# power_Rev_2.net
KiCad netlist of a schematic drawn in EAGLE
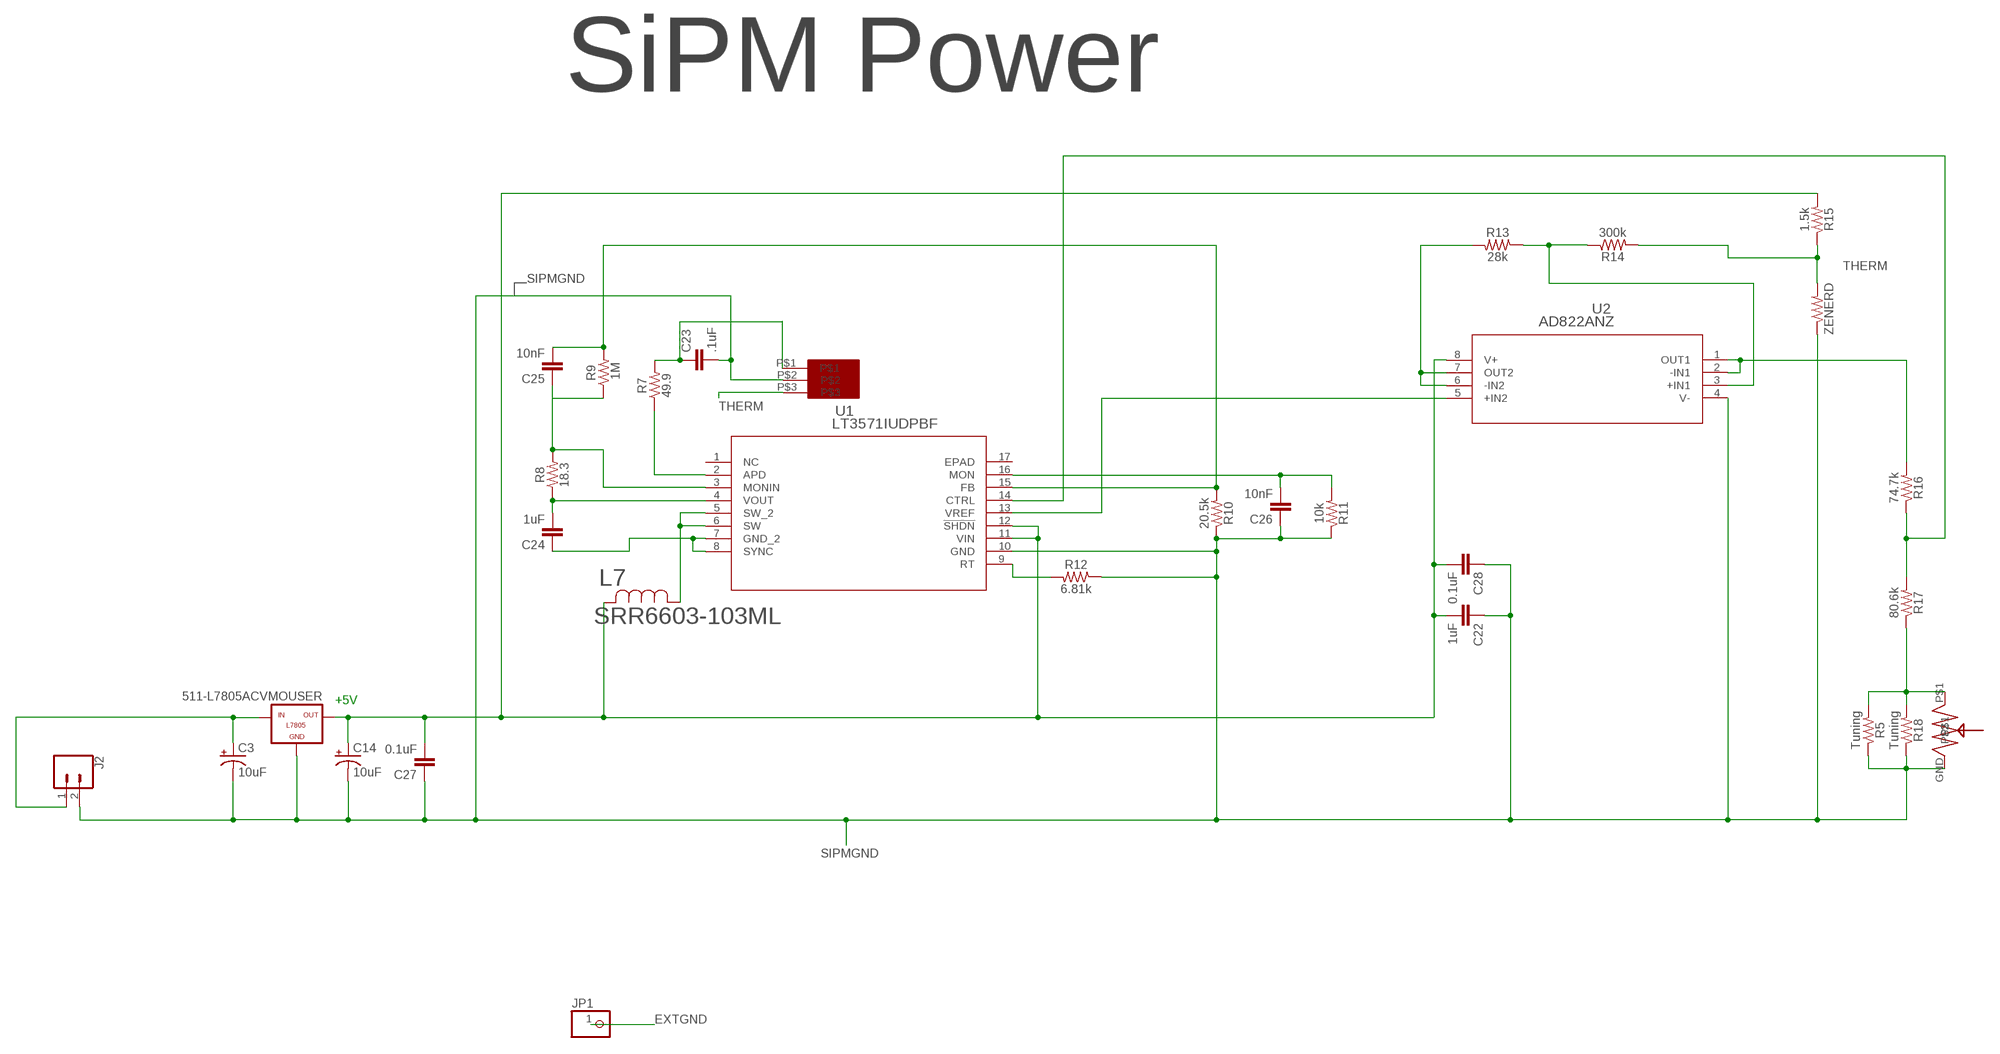
[diagram p0: schematic, sheet 1, part 1 of 2]
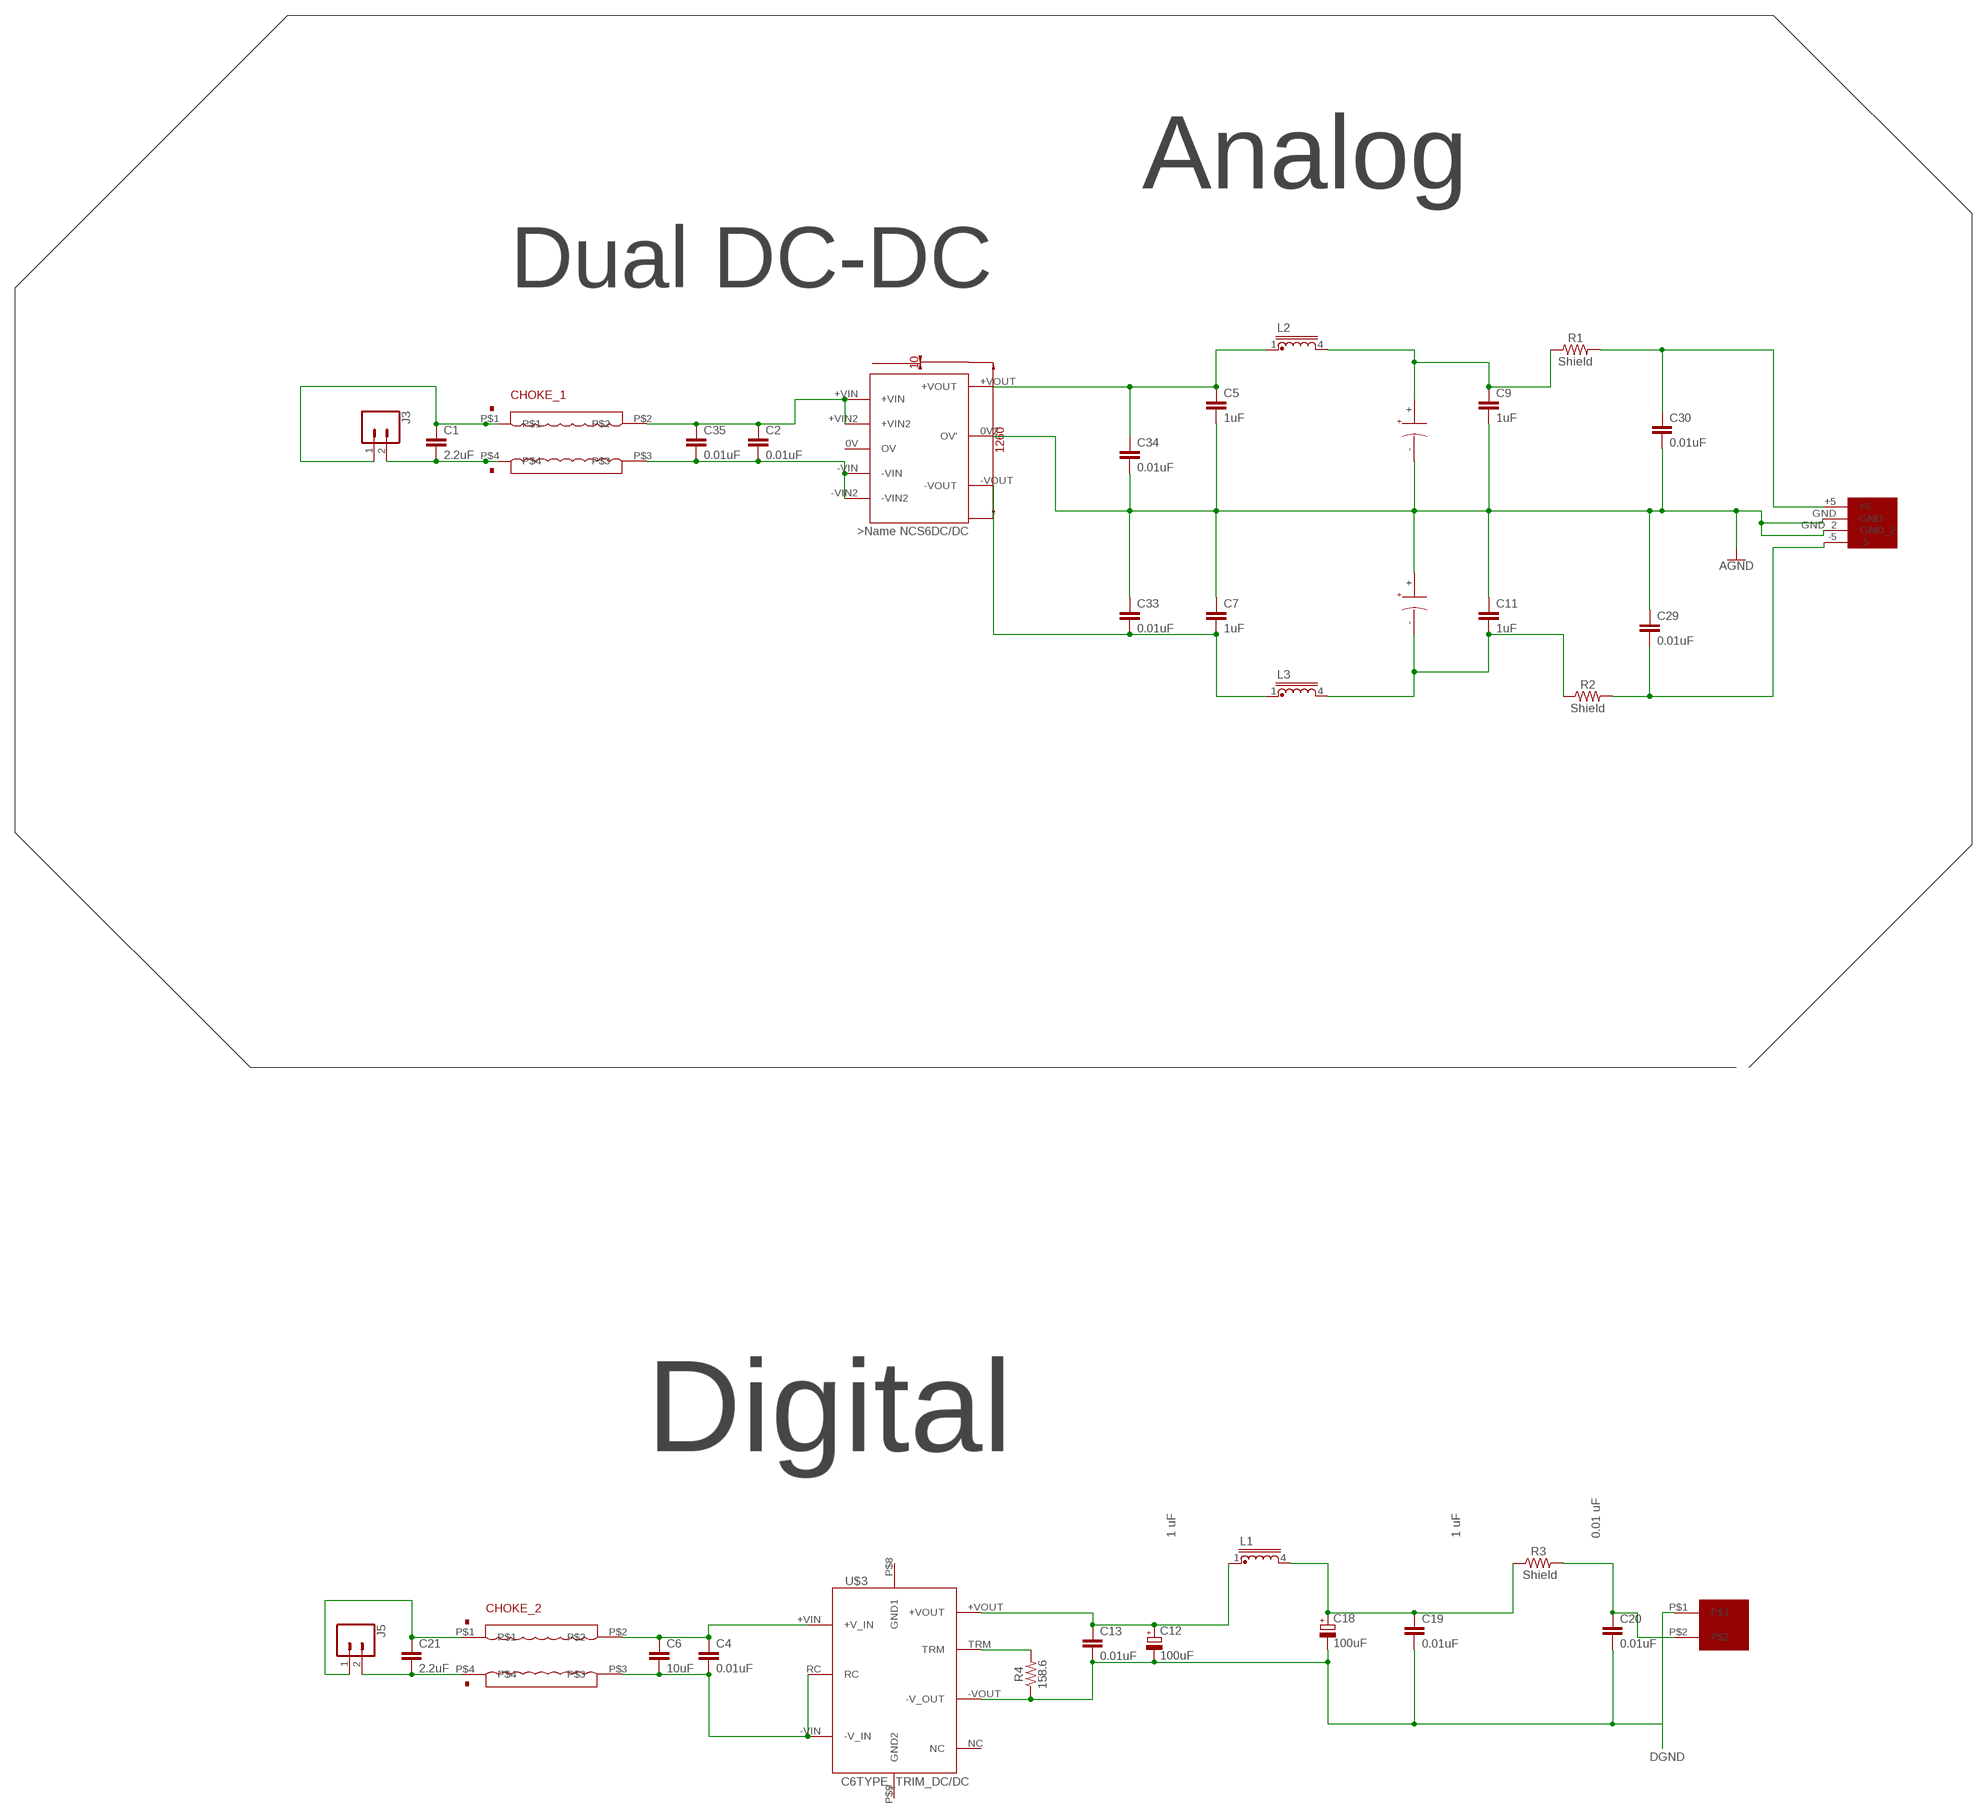
[diagram p1: schematic, sheet 1, part 2 of 2]

(export (version "E")
  (design (tool "Eeschema 10.0.6"))
  (components
    (comp (ref "511-L7805ACVMOUSER")
      (value "-L7805")
      (footprint "eagle-import:L7805")
      (libsource (lib "eagle-import") (part "-L7805"))
    )
    (comp (ref "C1")
      (value "2.2uF")
      (footprint "eagle-import:C050-024X044")
      (libsource (lib "eagle-import") (part "C-EU050-024X044"))
    )
    (comp (ref "C2")
      (value "0.01uF")
      (footprint "eagle-import:C025-025X050")
      (libsource (lib "eagle-import") (part "C-EU025-025X050"))
    )
    (comp (ref "C3")
      (value "10uF")
      (footprint "eagle-import:T_3528-12R")
      (libsource (lib "eagle-import") (part "CPOL-USB/3528-21R"))
    )
    (comp (ref "C4")
      (value "0.01uF")
      (footprint "eagle-import:C025-025X050")
      (libsource (lib "eagle-import") (part "C-EU025-025X050"))
    )
    (comp (ref "C5")
      (value "1uF")
      (footprint "eagle-import:C025-025X050")
      (libsource (lib "eagle-import") (part "C-EU025-025X050"))
    )
    (comp (ref "C6")
      (value "10uF")
      (footprint "eagle-import:C025-025X050")
      (libsource (lib "eagle-import") (part "C-EU025-025X050"))
    )
    (comp (ref "C7")
      (value "1uF")
      (footprint "eagle-import:C025-025X050")
      (libsource (lib "eagle-import") (part "C-EU025-025X050"))
    )
    (comp (ref "C8")
      (value "150uF")
      (footprint "eagle-import:399-3567-ND150UF")
      (libsource (lib "eagle-import") (part "399-4567-ND"))
    )
    (comp (ref "C9")
      (value "1uF")
      (footprint "eagle-import:C025-025X050")
      (libsource (lib "eagle-import") (part "C-EU025-025X050"))
    )
    (comp (ref "C10")
      (value "150uF")
      (footprint "eagle-import:399-3567-ND150UF")
      (libsource (lib "eagle-import") (part "399-4567-ND"))
    )
    (comp (ref "C11")
      (value "1uF")
      (footprint "eagle-import:C025-025X050")
      (libsource (lib "eagle-import") (part "C-EU025-025X050"))
    )
    (comp (ref "C12")
      (value "100uF")
      (footprint "eagle-import:C_6032-28R")
      (libsource (lib "eagle-import") (part "CPOL-EUC/6032-28R"))
    )
    (comp (ref "C13")
      (value "0.01uF")
      (footprint "eagle-import:C025-025X050")
      (libsource (lib "eagle-import") (part "C-EU025-025X050"))
    )
    (comp (ref "C14")
      (value "10uF")
      (footprint "eagle-import:T_3528-12R")
      (libsource (lib "eagle-import") (part "CPOL-USB/3528-21R"))
    )
    (comp (ref "C18")
      (value "100uF")
      (footprint "eagle-import:C_6032-28R")
      (fields (field (name "SPICEPREFIX") "C"))
      (libsource (lib "eagle-import") (part "CPOL-EUC/6032-28R"))
    )
    (comp (ref "C19")
      (value "0.01uF")
      (footprint "eagle-import:C025-025X050")
      (libsource (lib "eagle-import") (part "C-EU025-025X050"))
    )
    (comp (ref "C20")
      (value "0.01uF")
      (footprint "eagle-import:C025-025X050")
      (libsource (lib "eagle-import") (part "C-EU025-025X050"))
    )
    (comp (ref "C21")
      (value "2.2uF")
      (footprint "eagle-import:C050-024X044")
      (libsource (lib "eagle-import") (part "C-EU050-024X044"))
    )
    (comp (ref "C22")
      (value "1uF")
      (footprint "eagle-import:C025-025X050")
      (libsource (lib "eagle-import") (part "C-EU025-025X050"))
    )
    (comp (ref "C23")
      (value ".1uF")
      (footprint "eagle-import:C2.5-2")
      (libsource (lib "eagle-import") (part "C2.5/2"))
    )
    (comp (ref "C24")
      (value "1uF")
      (footprint "eagle-import:C025-025X050")
      (libsource (lib "eagle-import") (part "C-EU025-025X050"))
    )
    (comp (ref "C25")
      (value "10nF")
      (footprint "eagle-import:C2.5-2")
      (libsource (lib "eagle-import") (part "C2.5/2"))
    )
    (comp (ref "C26")
      (value "10nF")
      (footprint "eagle-import:C2.5-2")
      (libsource (lib "eagle-import") (part "C2.5/2"))
    )
    (comp (ref "C27")
      (value "0.1uF")
      (footprint "eagle-import:C2.5-2")
      (libsource (lib "eagle-import") (part "C2.5/2"))
    )
    (comp (ref "C28")
      (value "0.1uF")
      (footprint "eagle-import:C2.5-2")
      (libsource (lib "eagle-import") (part "C2.5/2"))
    )
    (comp (ref "C29")
      (value "0.01uF")
      (footprint "eagle-import:C0603")
      (libsource (lib "eagle-import") (part "C-EUC0603"))
    )
    (comp (ref "C30")
      (value "0.01uF")
      (footprint "eagle-import:C0603")
      (libsource (lib "eagle-import") (part "C-EUC0603"))
    )
    (comp (ref "C33")
      (value "0.01uF")
      (footprint "eagle-import:C0603")
      (libsource (lib "eagle-import") (part "C-EUC0603"))
    )
    (comp (ref "C34")
      (value "0.01uF")
      (footprint "eagle-import:C0603")
      (libsource (lib "eagle-import") (part "C-EUC0603"))
    )
    (comp (ref "C35")
      (value "0.01uF")
      (footprint "eagle-import:C0603")
      (libsource (lib "eagle-import") (part "C-EUC0603"))
    )
    (comp (ref "CHOKE_1")
      (value "DN4730-ND")
      (footprint "eagle-import:DN4730-ND")
      (libsource (lib "eagle-import") (part "DN4730-ND"))
    )
    (comp (ref "CHOKE_2")
      (value "DN4730-ND")
      (footprint "eagle-import:DN4730-ND")
      (libsource (lib "eagle-import") (part "DN4730-ND"))
    )
    (comp (ref "J2")
      (value "CONN_023.5MM")
      (footprint "eagle-import:SCREWTERMINAL-3.5MM-2")
      (libsource (lib "eagle-import") (part "CONN_023.5MM"))
    )
    (comp (ref "J3")
      (value "CONN_023.5MM")
      (footprint "eagle-import:SCREWTERMINAL-3.5MM-2")
      (libsource (lib "eagle-import") (part "CONN_023.5MM"))
    )
    (comp (ref "J5")
      (value "CONN_023.5MM")
      (footprint "eagle-import:SCREWTERMINAL-3.5MM-2")
      (libsource (lib "eagle-import") (part "CONN_023.5MM"))
    )
    (comp (ref "JP1")
      (value "PINHD-1X1")
      (footprint "eagle-import:1X01")
      (libsource (lib "eagle-import") (part "PINHD-1X1"))
    )
    (comp (ref "L1")
      (value "U15-CHOKE")
      (footprint "eagle-import:U15CHOKE")
      (libsource (lib "eagle-import") (part "U15-CHOKE"))
    )
    (comp (ref "L2")
      (value "U15-CHOKE")
      (footprint "eagle-import:U15CHOKE")
      (libsource (lib "eagle-import") (part "U15-CHOKE"))
    )
    (comp (ref "L3")
      (value "U15-CHOKE")
      (footprint "eagle-import:U15CHOKE")
      (libsource (lib "eagle-import") (part "U15-CHOKE"))
    )
    (comp (ref "L7")
      (value "SRR6603-103ML")
      (footprint "eagle-import:IND_BOURNS_SRR6603")
      (fields (field (name "MANUFACTURER_PART_NUMBER") "SRR6603103ML"))
      (libsource (lib "eagle-import") (part "SRR6603-103ML"))
    )
    (comp (ref "PWR_JACK")
      (value "WM403_NDPOWER_JACK")
      (footprint "eagle-import:WM4302-ND")
      (libsource (lib "eagle-import") (part "WM403_NDPOWER_JACK"))
    )
    (comp (ref "R1")
      (value "Shield")
      (footprint "eagle-import:AXIAL-0.3")
      (libsource (lib "eagle-import") (part "RESISTORAXIAL-0.3"))
    )
    (comp (ref "R2")
      (value "Shield")
      (footprint "eagle-import:AXIAL-0.3")
      (libsource (lib "eagle-import") (part "RESISTORAXIAL-0.3"))
    )
    (comp (ref "R3")
      (value "Shield")
      (footprint "eagle-import:AXIAL-0.3")
      (libsource (lib "eagle-import") (part "RESISTORAXIAL-0.3"))
    )
    (comp (ref "R4")
      (value "158.6")
      (footprint "eagle-import:AXIAL-0.3")
      (libsource (lib "eagle-import") (part "RESISTORAXIAL-0.3"))
    )
    (comp (ref "R5")
      (value "Tuning")
      (footprint "eagle-import:AXIAL-0.3")
      (libsource (lib "eagle-import") (part "RESISTORAXIAL-0.3"))
    )
    (comp (ref "R7")
      (value "49.9")
      (footprint "eagle-import:AXIAL-0.3")
      (libsource (lib "eagle-import") (part "RESISTORAXIAL-0.3"))
    )
    (comp (ref "R8")
      (value "18.3")
      (footprint "eagle-import:AXIAL-0.3")
      (libsource (lib "eagle-import") (part "RESISTORAXIAL-0.3"))
    )
    (comp (ref "R9")
      (value "1M")
      (footprint "eagle-import:AXIAL-0.3")
      (libsource (lib "eagle-import") (part "RESISTORAXIAL-0.3"))
    )
    (comp (ref "R10")
      (value "20.5k")
      (footprint "eagle-import:AXIAL-0.3")
      (libsource (lib "eagle-import") (part "RESISTORAXIAL-0.3"))
    )
    (comp (ref "R11")
      (value "10k")
      (footprint "eagle-import:AXIAL-0.3")
      (libsource (lib "eagle-import") (part "10KOHM-HORIZ-1/4W-1%"))
    )
    (comp (ref "R12")
      (value "6.81k")
      (footprint "eagle-import:AXIAL-0.3")
      (libsource (lib "eagle-import") (part "RESISTORAXIAL-0.3"))
    )
    (comp (ref "R13")
      (value "28k")
      (footprint "eagle-import:AXIAL-0.3")
      (libsource (lib "eagle-import") (part "RESISTORAXIAL-0.3"))
    )
    (comp (ref "R14")
      (value "300k")
      (footprint "eagle-import:AXIAL-0.3")
      (libsource (lib "eagle-import") (part "RESISTORAXIAL-0.3"))
    )
    (comp (ref "R15")
      (value "1.5k")
      (footprint "eagle-import:AXIAL-0.3")
      (libsource (lib "eagle-import") (part "RESISTORAXIAL-0.3"))
    )
    (comp (ref "R16")
      (value "74.7k")
      (footprint "eagle-import:AXIAL-0.3")
      (libsource (lib "eagle-import") (part "RESISTORAXIAL-0.3"))
    )
    (comp (ref "R17")
      (value "80.6k")
      (footprint "eagle-import:AXIAL-0.3")
      (libsource (lib "eagle-import") (part "RESISTORAXIAL-0.3"))
    )
    (comp (ref "R18")
      (value "Tuning")
      (footprint "eagle-import:AXIAL-0.3")
      (libsource (lib "eagle-import") (part "RESISTORAXIAL-0.3"))
    )
    (comp (ref "U$1")
      (value "NCS6D1205")
      (footprint "eagle-import:NCS6D1205C")
      (libsource (lib "eagle-import") (part "NCS6D1205"))
    )
    (comp (ref "U$3")
      (value "C6TYPE_TRIM_DC/DC")
      (footprint "eagle-import:CONV_DC_DC_6W_SNGL_C6TYPE")
      (libsource (lib "eagle-import") (part "C6TYPE_TRIM_DC/DC"))
    )
    (comp (ref "U$4")
      (value "WM4300-ND_2PIN")
      (footprint "eagle-import:WM4300-ND_2PIN")
      (libsource (lib "eagle-import") (part "WM4300-ND_2PIN"))
    )
    (comp (ref "U$5")
      (value "WM4301-ND_3PIN")
      (footprint "eagle-import:WM4301-ND_3PIN")
      (libsource (lib "eagle-import") (part "WM4301-ND_3PIN"))
    )
    (comp (ref "U1")
      (value "LT3571IUDPBF")
      (footprint "eagle-import:QFN-16_UD")
      (fields (field (name "MANUFACTURER_PART_NUMBER") "LT3571IUD#PBF"))
      (libsource (lib "eagle-import") (part "LT3571IUDPBF"))
    )
    (comp (ref "U2")
      (value "AD822ANZ")
      (footprint "eagle-import:N_8")
      (libsource (lib "eagle-import") (part "AD822ANZ"))
    )
    (comp (ref "VAR1")
      (value "10KTRIM_POT")
      (footprint "eagle-import:10KTRIM_POT")
      (libsource (lib "eagle-import") (part "10KTRIM_POT"))
    )
    (comp (ref "ZENERD")
      (value "RESISTORAXIAL-0.3")
      (footprint "eagle-import:AXIAL-0.3")
      (libsource (lib "eagle-import") (part "RESISTORAXIAL-0.3"))
    )
  )
  (nets
    (net (code "1") (name "/DGND") (class "Default")
      (node (ref "C12") (pin "-") (pinfunction "-_-") (pintype "passive"))
      (node (ref "C13") (pin "2") (pinfunction "2_2") (pintype "passive"))
      (node (ref "C18") (pin "-") (pinfunction "-_-") (pintype "passive"))
      (node (ref "C19") (pin "2") (pinfunction "2_2") (pintype "passive"))
      (node (ref "C20") (pin "2") (pinfunction "2_2") (pintype "passive"))
      (node (ref "R4") (pin "P$1") (pinfunction "1_P$1") (pintype "passive"))
      (node (ref "U$3") (pin "-VOUT") (pinfunction "-V_OUT_-VOUT") (pintype "bidirectional"))
      (node (ref "U$4") (pin "P$1") (pinfunction "P$1_P$1") (pintype "bidirectional"))
    )
    (net (code "2") (name "/EXTGND") (class "Default")
      (node (ref "JP1") (pin "1") (pinfunction "1_1") (pintype "passive"))
    )
    (net (code "3") (name "/SIPMGND") (class "Default")
      (node (ref "511-L7805ACVMOUSER") (pin "GND") (pinfunction "GND_GND") (pintype "input"))
      (node (ref "C14") (pin "-") (pinfunction "-_-") (pintype "passive"))
      (node (ref "C22") (pin "1") (pinfunction "1_1") (pintype "passive"))
      (node (ref "C23") (pin "2") (pinfunction "2_2") (pintype "passive"))
      (node (ref "C26") (pin "1") (pinfunction "1_1") (pintype "passive"))
      (node (ref "C27") (pin "1") (pinfunction "1_1") (pintype "passive"))
      (node (ref "C28") (pin "1") (pinfunction "1_1") (pintype "passive"))
      (node (ref "C3") (pin "-") (pinfunction "-_-") (pintype "passive"))
      (node (ref "J2") (pin "2") (pinfunction "2_2") (pintype "passive"))
      (node (ref "R10") (pin "P$1") (pinfunction "1_P$1") (pintype "passive"))
      (node (ref "R11") (pin "P$1") (pinfunction "1_P$1") (pintype "passive"))
      (node (ref "R12") (pin "P$1") (pinfunction "1_P$1") (pintype "passive"))
      (node (ref "R18") (pin "P$1") (pinfunction "1_P$1") (pintype "passive"))
      (node (ref "R5") (pin "P$1") (pinfunction "1_P$1") (pintype "passive"))
      (node (ref "U$5") (pin "P$2") (pinfunction "P$2_P$2") (pintype "bidirectional"))
      (node (ref "U1") (pin "10") (pinfunction "GND_10") (pintype "power_in"))
      (node (ref "U2") (pin "4") (pinfunction "V-_4") (pintype "power_in"))
      (node (ref "VAR1") (pin "GND") (pinfunction "P$2_GND") (pintype "bidirectional"))
      (node (ref "ZENERD") (pin "P$1") (pinfunction "1_P$1") (pintype "passive"))
    )
    (net (code "4") (name "/THERM") (class "Default")
      (node (ref "R14") (pin "P$2") (pinfunction "2_P$2") (pintype "passive"))
      (node (ref "R15") (pin "P$1") (pinfunction "1_P$1") (pintype "passive"))
      (node (ref "U$5") (pin "P$3") (pinfunction "P$3_P$3") (pintype "bidirectional"))
      (node (ref "ZENERD") (pin "P$2") (pinfunction "2_P$2") (pintype "passive"))
    )
    (net (code "5") (name "AGND") (class "Default")
      (node (ref "C10") (pin "+") (pinfunction "P_+") (pintype "bidirectional"))
      (node (ref "C11") (pin "1") (pinfunction "1_1") (pintype "passive"))
      (node (ref "C29") (pin "1") (pinfunction "1_1") (pintype "passive"))
      (node (ref "C30") (pin "2") (pinfunction "2_2") (pintype "passive"))
      (node (ref "C33") (pin "1") (pinfunction "1_1") (pintype "passive"))
      (node (ref "C34") (pin "2") (pinfunction "2_2") (pintype "passive"))
      (node (ref "C5") (pin "2") (pinfunction "2_2") (pintype "passive"))
      (node (ref "C7") (pin "1") (pinfunction "1_1") (pintype "passive"))
      (node (ref "C8") (pin "-") (pinfunction "N_-") (pintype "bidirectional"))
      (node (ref "C9") (pin "2") (pinfunction "2_2") (pintype "passive"))
      (node (ref "PWR_JACK") (pin "GND") (pinfunction "GND_GND") (pintype "bidirectional"))
      (node (ref "PWR_JACK") (pin "GND_2") (pinfunction "GND_2_GND_2") (pintype "bidirectional"))
      (node (ref "U$1") (pin "0V2") (pinfunction "OV'_0V2") (pintype "bidirectional"))
    )
    (net (code "6") (name "Net-(511-L7805ACVMOUSER-PadIN)") (class "Default")
      (node (ref "511-L7805ACVMOUSER") (pin "IN") (pinfunction "IN_IN") (pintype "input"))
      (node (ref "C3") (pin "+") (pinfunction "+_+") (pintype "passive"))
      (node (ref "J2") (pin "1") (pinfunction "1_1") (pintype "passive"))
    )
    (net (code "7") (name "Net-(C1-Pad1)") (class "Default")
      (node (ref "C1") (pin "1") (pinfunction "1_1") (pintype "passive"))
      (node (ref "CHOKE_1") (pin "P$1") (pinfunction "P$1_P$1") (pintype "bidirectional"))
      (node (ref "J3") (pin "1") (pinfunction "1_1") (pintype "passive"))
    )
    (net (code "8") (name "Net-(C1-Pad2)") (class "Default")
      (node (ref "C1") (pin "2") (pinfunction "2_2") (pintype "passive"))
      (node (ref "CHOKE_1") (pin "P$4") (pinfunction "P$4_P$4") (pintype "bidirectional"))
      (node (ref "J3") (pin "2") (pinfunction "2_2") (pintype "passive"))
    )
    (net (code "9") (name "Net-(C2-Pad1)") (class "Default")
      (node (ref "C2") (pin "1") (pinfunction "1_1") (pintype "passive"))
      (node (ref "C35") (pin "1") (pinfunction "1_1") (pintype "passive"))
      (node (ref "CHOKE_1") (pin "P$2") (pinfunction "P$2_P$2") (pintype "bidirectional"))
      (node (ref "U$1") (pin "+VIN") (pinfunction "+VIN_+VIN") (pintype "power_in"))
      (node (ref "U$1") (pin "+VIN2") (pinfunction "+VIN2_+VIN2") (pintype "power_in"))
    )
    (net (code "10") (name "Net-(C2-Pad2)") (class "Default")
      (node (ref "C2") (pin "2") (pinfunction "2_2") (pintype "passive"))
      (node (ref "C35") (pin "2") (pinfunction "2_2") (pintype "passive"))
      (node (ref "CHOKE_1") (pin "P$3") (pinfunction "P$3_P$3") (pintype "bidirectional"))
      (node (ref "U$1") (pin "-VIN") (pinfunction "-VIN_-VIN") (pintype "bidirectional"))
      (node (ref "U$1") (pin "-VIN2") (pinfunction "-VIN2_-VIN2") (pintype "bidirectional"))
    )
    (net (code "11") (name "Net-(C8-P)") (class "Default")
      (node (ref "C8") (pin "+") (pinfunction "P_+") (pintype "bidirectional"))
      (node (ref "C9") (pin "1") (pinfunction "1_1") (pintype "passive"))
      (node (ref "L2") (pin "4") (pinfunction "4_4") (pintype "passive"))
      (node (ref "R1") (pin "P$1") (pinfunction "1_P$1") (pintype "passive"))
    )
    (net (code "12") (name "Net-(C10-N)") (class "Default")
      (node (ref "C10") (pin "-") (pinfunction "N_-") (pintype "bidirectional"))
      (node (ref "C11") (pin "2") (pinfunction "2_2") (pintype "passive"))
      (node (ref "L3") (pin "4") (pinfunction "4_4") (pintype "passive"))
      (node (ref "R2") (pin "P$1") (pinfunction "1_P$1") (pintype "passive"))
    )
    (net (code "13") (name "Net-(C12-Pad+)") (class "Default")
      (node (ref "C12") (pin "+") (pinfunction "+_+") (pintype "passive"))
      (node (ref "C13") (pin "1") (pinfunction "1_1") (pintype "passive"))
      (node (ref "L1") (pin "1") (pinfunction "1_1") (pintype "passive"))
      (node (ref "U$3") (pin "+VOUT") (pinfunction "+VOUT_+VOUT") (pintype "bidirectional"))
    )
    (net (code "14") (name "Net-(C21-Pad1)") (class "Default")
      (node (ref "C21") (pin "1") (pinfunction "1_1") (pintype "passive"))
      (node (ref "CHOKE_2") (pin "P$1") (pinfunction "P$1_P$1") (pintype "bidirectional"))
      (node (ref "J5") (pin "1") (pinfunction "1_1") (pintype "passive"))
    )
    (net (code "15") (name "Net-(C21-Pad2)") (class "Default")
      (node (ref "C21") (pin "2") (pinfunction "2_2") (pintype "passive"))
      (node (ref "CHOKE_2") (pin "P$4") (pinfunction "P$4_P$4") (pintype "bidirectional"))
      (node (ref "J5") (pin "2") (pinfunction "2_2") (pintype "passive"))
    )
    (net (code "16") (name "Net-(C33-Pad2)") (class "Default")
      (node (ref "C33") (pin "2") (pinfunction "2_2") (pintype "passive"))
      (node (ref "C7") (pin "2") (pinfunction "2_2") (pintype "passive"))
      (node (ref "L3") (pin "1") (pinfunction "1_1") (pintype "passive"))
      (node (ref "U$1") (pin "-VOUT") (pinfunction "-VOUT_-VOUT") (pintype "bidirectional"))
    )
    (net (code "17") (name "Net-(C34-Pad1)") (class "Default")
      (node (ref "C34") (pin "1") (pinfunction "1_1") (pintype "passive"))
      (node (ref "C5") (pin "1") (pinfunction "1_1") (pintype "passive"))
      (node (ref "L2") (pin "1") (pinfunction "1_1") (pintype "passive"))
      (node (ref "U$1") (pin "+VOUT") (pinfunction "+VOUT_+VOUT") (pintype "bidirectional"))
    )
    (net (code "18") (name "Net-(R1-2)") (class "Default")
      (node (ref "C30") (pin "1") (pinfunction "1_1") (pintype "passive"))
      (node (ref "PWR_JACK") (pin "+5") (pinfunction "+5_+5") (pintype "bidirectional"))
      (node (ref "R1") (pin "P$2") (pinfunction "2_P$2") (pintype "passive"))
    )
    (net (code "19") (name "Net-(R2-2)") (class "Default")
      (node (ref "C29") (pin "2") (pinfunction "2_2") (pintype "passive"))
      (node (ref "PWR_JACK") (pin "-5") (pinfunction "-5_-5") (pintype "bidirectional"))
      (node (ref "R2") (pin "P$2") (pinfunction "2_P$2") (pintype "passive"))
    )
    (net (code "20") (name "Net-(R3-1)") (class "Default")
      (node (ref "C18") (pin "+") (pinfunction "+_+") (pintype "passive"))
      (node (ref "C19") (pin "1") (pinfunction "1_1") (pintype "passive"))
      (node (ref "L1") (pin "4") (pinfunction "4_4") (pintype "passive"))
      (node (ref "R3") (pin "P$1") (pinfunction "1_P$1") (pintype "passive"))
    )
    (net (code "21") (name "Net-(R3-2)") (class "Default")
      (node (ref "C20") (pin "1") (pinfunction "1_1") (pintype "passive"))
      (node (ref "R3") (pin "P$2") (pinfunction "2_P$2") (pintype "passive"))
      (node (ref "U$4") (pin "P$2") (pinfunction "P$2_P$2") (pintype "bidirectional"))
    )
    (net (code "22") (name "Net-(R4-2)") (class "Default")
      (node (ref "R4") (pin "P$2") (pinfunction "2_P$2") (pintype "passive"))
      (node (ref "U$3") (pin "TRM") (pinfunction "TRM_TRM") (pintype "bidirectional"))
    )
    (net (code "23") (name "Net-(R7-1)") (class "Default")
      (node (ref "R7") (pin "P$1") (pinfunction "1_P$1") (pintype "passive"))
      (node (ref "U1") (pin "2") (pinfunction "APD_2") (pintype "passive"))
    )
    (net (code "24") (name "Net-(R7-2)") (class "Default")
      (node (ref "C23") (pin "1") (pinfunction "1_1") (pintype "passive"))
      (node (ref "R7") (pin "P$2") (pinfunction "2_P$2") (pintype "passive"))
      (node (ref "U$5") (pin "P$1") (pinfunction "P$1_P$1") (pintype "bidirectional"))
    )
    (net (code "25") (name "Net-(R8-1)") (class "Default")
      (node (ref "C24") (pin "2") (pinfunction "2_2") (pintype "passive"))
      (node (ref "R8") (pin "P$1") (pinfunction "1_P$1") (pintype "passive"))
      (node (ref "U1") (pin "4") (pinfunction "VOUT_4") (pintype "output"))
    )
    (net (code "26") (name "Net-(R8-2)") (class "Default")
      (node (ref "C25") (pin "1") (pinfunction "1_1") (pintype "passive"))
      (node (ref "R8") (pin "P$2") (pinfunction "2_P$2") (pintype "passive"))
      (node (ref "R9") (pin "P$1") (pinfunction "1_P$1") (pintype "passive"))
      (node (ref "U1") (pin "3") (pinfunction "MONIN_3") (pintype "input"))
    )
    (net (code "27") (name "Net-(R10-2)") (class "Default")
      (node (ref "C25") (pin "2") (pinfunction "2_2") (pintype "passive"))
      (node (ref "R10") (pin "P$2") (pinfunction "2_P$2") (pintype "passive"))
      (node (ref "R9") (pin "P$2") (pinfunction "2_P$2") (pintype "passive"))
      (node (ref "U1") (pin "15") (pinfunction "FB_15") (pintype "output"))
    )
    (net (code "28") (name "Net-(R11-2)") (class "Default")
      (node (ref "C26") (pin "2") (pinfunction "2_2") (pintype "passive"))
      (node (ref "R11") (pin "P$2") (pinfunction "2_P$2") (pintype "passive"))
      (node (ref "U1") (pin "16") (pinfunction "MON_16") (pintype "output"))
    )
    (net (code "29") (name "Net-(R12-2)") (class "Default")
      (node (ref "R12") (pin "P$2") (pinfunction "2_P$2") (pintype "passive"))
      (node (ref "U1") (pin "9") (pinfunction "RT_9") (pintype "passive"))
    )
    (net (code "30") (name "Net-(R13-1)") (class "Default")
      (node (ref "R13") (pin "P$1") (pinfunction "1_P$1") (pintype "passive"))
      (node (ref "R14") (pin "P$1") (pinfunction "1_P$1") (pintype "passive"))
      (node (ref "U2") (pin "3") (pinfunction "+IN1_3") (pintype "passive"))
    )
    (net (code "31") (name "Net-(R13-2)") (class "Default")
      (node (ref "R13") (pin "P$2") (pinfunction "2_P$2") (pintype "passive"))
      (node (ref "U2") (pin "6") (pinfunction "-IN2_6") (pintype "passive"))
      (node (ref "U2") (pin "7") (pinfunction "OUT2_7") (pintype "passive"))
    )
    (net (code "32") (name "Net-(R15-2)") (class "Default")
      (node (ref "511-L7805ACVMOUSER") (pin "OUT") (pinfunction "OUT_OUT") (pintype "passive"))
      (node (ref "C14") (pin "+") (pinfunction "+_+") (pintype "passive"))
      (node (ref "C22") (pin "2") (pinfunction "2_2") (pintype "passive"))
      (node (ref "C27") (pin "2") (pinfunction "2_2") (pintype "passive"))
      (node (ref "C28") (pin "2") (pinfunction "2_2") (pintype "passive"))
      (node (ref "L7") (pin "2") (pinfunction "2_2") (pintype "passive"))
      (node (ref "R15") (pin "P$2") (pinfunction "2_P$2") (pintype "passive"))
      (node (ref "U1") (pin "11") (pinfunction "VIN_11") (pintype "input"))
      (node (ref "U1") (pin "12") (pinfunction "~{SHDN}_12") (pintype "passive"))
      (node (ref "U2") (pin "8") (pinfunction "V+_8") (pintype "power_in"))
    )
    (net (code "33") (name "Net-(R16-1)") (class "Default")
      (node (ref "R16") (pin "P$1") (pinfunction "1_P$1") (pintype "passive"))
      (node (ref "R17") (pin "P$2") (pinfunction "2_P$2") (pintype "passive"))
      (node (ref "U1") (pin "14") (pinfunction "CTRL_14") (pintype "output"))
    )
    (net (code "34") (name "Net-(R16-2)") (class "Default")
      (node (ref "R16") (pin "P$2") (pinfunction "2_P$2") (pintype "passive"))
      (node (ref "U2") (pin "1") (pinfunction "OUT1_1") (pintype "passive"))
      (node (ref "U2") (pin "2") (pinfunction "-IN1_2") (pintype "passive"))
    )
    (net (code "35") (name "Net-(R17-1)") (class "Default")
      (node (ref "R17") (pin "P$1") (pinfunction "1_P$1") (pintype "passive"))
      (node (ref "R18") (pin "P$2") (pinfunction "2_P$2") (pintype "passive"))
      (node (ref "R5") (pin "P$2") (pinfunction "2_P$2") (pintype "passive"))
      (node (ref "VAR1") (pin "P$1") (pinfunction "P$1_P$1") (pintype "bidirectional"))
    )
    (net (code "36") (name "Net-(U$3-+V_IN)") (class "Default")
      (node (ref "C4") (pin "1") (pinfunction "1_1") (pintype "passive"))
      (node (ref "C6") (pin "1") (pinfunction "1_1") (pintype "passive"))
      (node (ref "CHOKE_2") (pin "P$2") (pinfunction "P$2_P$2") (pintype "bidirectional"))
      (node (ref "U$3") (pin "+VIN") (pinfunction "+V_IN_+VIN") (pintype "bidirectional"))
    )
    (net (code "37") (name "Net-(U$3--V_IN)") (class "Default")
      (node (ref "C4") (pin "2") (pinfunction "2_2") (pintype "passive"))
      (node (ref "C6") (pin "2") (pinfunction "2_2") (pintype "passive"))
      (node (ref "CHOKE_2") (pin "P$3") (pinfunction "P$3_P$3") (pintype "bidirectional"))
      (node (ref "U$3") (pin "-VIN") (pinfunction "-V_IN_-VIN") (pintype "bidirectional"))
      (node (ref "U$3") (pin "RC") (pinfunction "RC_RC") (pintype "bidirectional"))
    )
    (net (code "38") (name "Net-(U1-GND_2)") (class "Default")
      (node (ref "C24") (pin "1") (pinfunction "1_1") (pintype "passive"))
      (node (ref "U1") (pin "7") (pinfunction "GND_2_7") (pintype "power_in"))
      (node (ref "U1") (pin "8") (pinfunction "SYNC_8") (pintype "passive"))
    )
    (net (code "39") (name "Net-(U1-SW)") (class "Default")
      (node (ref "L7") (pin "1") (pinfunction "1_1") (pintype "passive"))
      (node (ref "U1") (pin "5") (pinfunction "SW_2_5") (pintype "passive"))
      (node (ref "U1") (pin "6") (pinfunction "SW_6") (pintype "passive"))
    )
    (net (code "40") (name "Net-(U1-VREF)") (class "Default")
      (node (ref "U1") (pin "13") (pinfunction "VREF_13") (pintype "output"))
      (node (ref "U2") (pin "5") (pinfunction "+IN2_5") (pintype "passive"))
    )
    (net (code "41") (name "unconnected-(U$1-OV-Pad0V)") (class "Default")
      (node (ref "U$1") (pin "0V") (pinfunction "OV_0V") (pintype "bidirectional"))
    )
    (net (code "42") (name "unconnected-(U$3-GND1-PadP$8)") (class "Default")
      (node (ref "U$3") (pin "P$8") (pinfunction "GND1_P$8") (pintype "bidirectional"))
    )
    (net (code "43") (name "unconnected-(U$3-GND2-PadP$9)") (class "Default")
      (node (ref "U$3") (pin "P$9") (pinfunction "GND2_P$9") (pintype "bidirectional"))
    )
    (net (code "44") (name "unconnected-(U$3-PadNC)") (class "Default")
      (node (ref "U$3") (pin "NC") (pinfunction "NC_NC") (pintype "bidirectional"))
    )
    (net (code "45") (name "unconnected-(U1-EPAD-Pad17)") (class "Default")
      (node (ref "U1") (pin "17") (pinfunction "EPAD_17") (pintype "passive"))
    )
    (net (code "46") (name "unconnected-(U1-NC-Pad1)") (class "Default")
      (node (ref "U1") (pin "1") (pinfunction "NC_1") (pintype "no_connect"))
    )
  )
)
